# SwitchNode_Shield.net
KiCad netlist of a schematic drawn in EAGLE
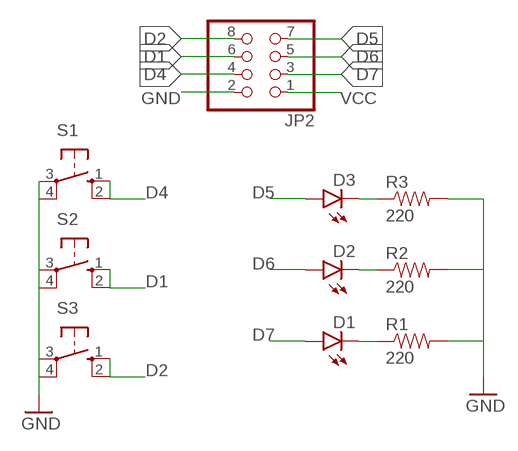
[diagram p0: schematic, sheet 1]

(export (version "E")
  (design (tool "Eeschema 10.0.6"))
  (components
    (comp (ref "D1")
      (value "LED3MM")
      (footprint "eagle-import:LED3MM")
      (libsource (lib "eagle-import") (part "LED3MM"))
    )
    (comp (ref "D2")
      (value "LED3MM")
      (footprint "eagle-import:LED3MM")
      (libsource (lib "eagle-import") (part "LED3MM"))
    )
    (comp (ref "D3")
      (value "LED3MM")
      (footprint "eagle-import:LED3MM")
      (libsource (lib "eagle-import") (part "LED3MM"))
    )
    (comp (ref "JP2")
      (value "PINHD-2X4")
      (footprint "eagle-import:2X04")
      (libsource (lib "eagle-import") (part "PINHD-2X4"))
    )
    (comp (ref "R1")
      (value "220")
      (footprint "eagle-import:AXIAL-0.3")
      (libsource (lib "eagle-import") (part "RESISTORAXIAL-0.3"))
    )
    (comp (ref "R2")
      (value "220")
      (footprint "eagle-import:AXIAL-0.3")
      (libsource (lib "eagle-import") (part "RESISTORAXIAL-0.3"))
    )
    (comp (ref "R3")
      (value "220")
      (footprint "eagle-import:AXIAL-0.3")
      (libsource (lib "eagle-import") (part "RESISTORAXIAL-0.3"))
    )
    (comp (ref "S1")
      (value "40-XX")
      (footprint "eagle-import:B3F-40XX")
      (fields (field (name "MF") "OMRON COMPONENTS USA") (field (name "MPN") "B3F-4000"))
      (libsource (lib "eagle-import") (part "40-XX"))
    )
    (comp (ref "S2")
      (value "40-XX")
      (footprint "eagle-import:B3F-40XX")
      (fields (field (name "MF") "OMRON COMPONENTS USA") (field (name "MPN") "B3F-4000"))
      (libsource (lib "eagle-import") (part "40-XX"))
    )
    (comp (ref "S3")
      (value "40-XX")
      (footprint "eagle-import:B3F-40XX")
      (fields (field (name "MF") "OMRON COMPONENTS USA") (field (name "MPN") "B3F-4000"))
      (libsource (lib "eagle-import") (part "40-XX"))
    )
  )
  (nets
    (net (code "1") (name "/VCC") (class "Default")
      (node (ref "JP2") (pin "1") (pinfunction "1_1") (pintype "passive"))
    )
    (net (code "2") (name "D1") (class "Default")
      (node (ref "JP2") (pin "6") (pinfunction "6_6") (pintype "passive"))
      (node (ref "S2") (pin "1") (pinfunction "S_1") (pintype "passive"))
      (node (ref "S2") (pin "2") (pinfunction "S1_2") (pintype "passive"))
    )
    (net (code "3") (name "D2") (class "Default")
      (node (ref "JP2") (pin "8") (pinfunction "8_8") (pintype "passive"))
      (node (ref "S3") (pin "1") (pinfunction "S_1") (pintype "passive"))
      (node (ref "S3") (pin "2") (pinfunction "S1_2") (pintype "passive"))
    )
    (net (code "4") (name "D4") (class "Default")
      (node (ref "JP2") (pin "4") (pinfunction "4_4") (pintype "passive"))
      (node (ref "S1") (pin "1") (pinfunction "S_1") (pintype "passive"))
      (node (ref "S1") (pin "2") (pinfunction "S1_2") (pintype "passive"))
    )
    (net (code "5") (name "D5") (class "Default")
      (node (ref "D3") (pin "A") (pinfunction "A_A") (pintype "passive"))
      (node (ref "JP2") (pin "7") (pinfunction "7_7") (pintype "passive"))
    )
    (net (code "6") (name "D6") (class "Default")
      (node (ref "D2") (pin "A") (pinfunction "A_A") (pintype "passive"))
      (node (ref "JP2") (pin "5") (pinfunction "5_5") (pintype "passive"))
    )
    (net (code "7") (name "D7") (class "Default")
      (node (ref "D1") (pin "A") (pinfunction "A_A") (pintype "passive"))
      (node (ref "JP2") (pin "3") (pinfunction "3_3") (pintype "passive"))
    )
    (net (code "8") (name "GND") (class "Default")
      (node (ref "JP2") (pin "2") (pinfunction "2_2") (pintype "passive"))
      (node (ref "R1") (pin "P$2") (pinfunction "2_P$2") (pintype "passive"))
      (node (ref "R2") (pin "P$2") (pinfunction "2_P$2") (pintype "passive"))
      (node (ref "R3") (pin "P$2") (pinfunction "2_P$2") (pintype "passive"))
      (node (ref "S1") (pin "3") (pinfunction "P_3") (pintype "passive"))
      (node (ref "S1") (pin "4") (pinfunction "P1_4") (pintype "passive"))
      (node (ref "S2") (pin "3") (pinfunction "P_3") (pintype "passive"))
      (node (ref "S2") (pin "4") (pinfunction "P1_4") (pintype "passive"))
      (node (ref "S3") (pin "3") (pinfunction "P_3") (pintype "passive"))
      (node (ref "S3") (pin "4") (pinfunction "P1_4") (pintype "passive"))
    )
    (net (code "9") (name "Net-(D1-C)") (class "Default")
      (node (ref "D1") (pin "K") (pinfunction "C_K") (pintype "passive"))
      (node (ref "R1") (pin "P$1") (pinfunction "1_P$1") (pintype "passive"))
    )
    (net (code "10") (name "Net-(D2-C)") (class "Default")
      (node (ref "D2") (pin "K") (pinfunction "C_K") (pintype "passive"))
      (node (ref "R2") (pin "P$1") (pinfunction "1_P$1") (pintype "passive"))
    )
    (net (code "11") (name "Net-(D3-C)") (class "Default")
      (node (ref "D3") (pin "K") (pinfunction "C_K") (pintype "passive"))
      (node (ref "R3") (pin "P$1") (pinfunction "1_P$1") (pintype "passive"))
    )
  )
)
